# ExperimentBoard.net
KiCad netlist of a schematic drawn in Altium Designer
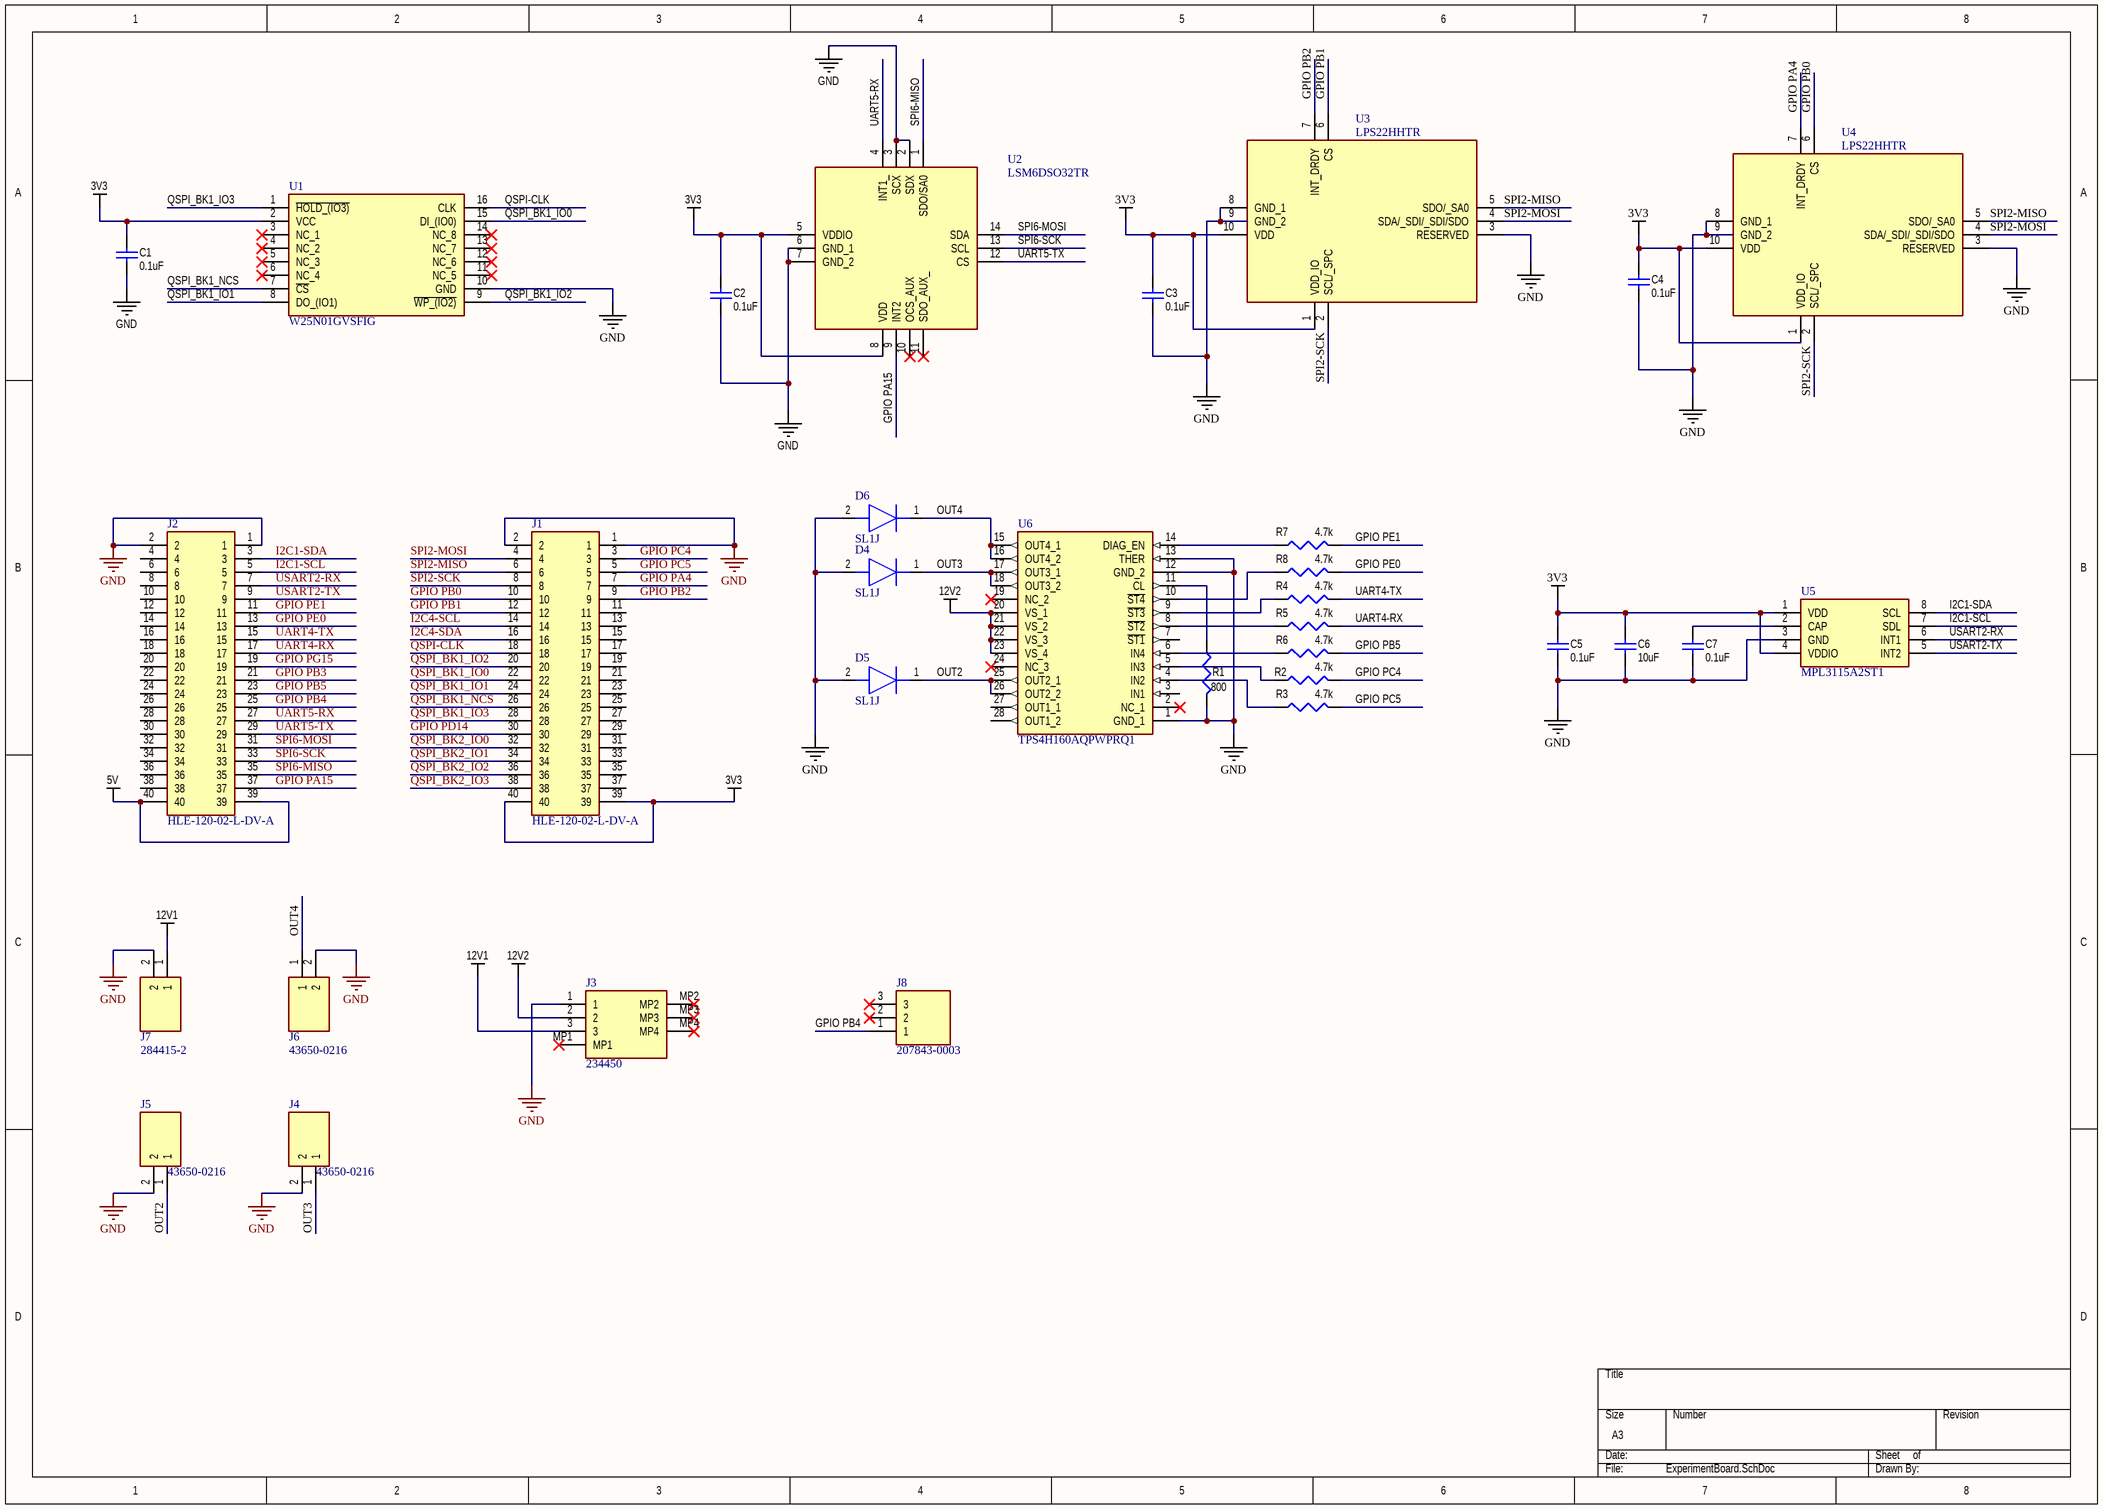
[diagram p0: ExperimentBoard.SchDoc]

(export (version "E")
  (design (tool "Eeschema 10.0.6"))
  (components
    (comp (ref "C1")
      (value "0.1uF")
      (footprint "1608[0603]")
      (description "Capacitor")
      (fields (field (name "PUBLISHER") "Altium Limited"))
      (libsource (lib "Miscellaneous Devices") (part "Cap"))
    )
    (comp (ref "C2")
      (value "0.1uF")
      (footprint "1608[0603]")
      (description "Capacitor")
      (fields (field (name "PUBLISHER") "Altium Limited"))
      (libsource (lib "Miscellaneous Devices") (part "Cap"))
    )
    (comp (ref "C3")
      (value "0.1uF")
      (footprint "1608[0603]")
      (description "Capacitor")
      (fields (field (name "PUBLISHER") "Altium Limited"))
      (libsource (lib "Miscellaneous Devices") (part "Cap"))
    )
    (comp (ref "C4")
      (value "0.1uF")
      (footprint "1608[0603]")
      (description "Capacitor")
      (fields (field (name "PUBLISHER") "Altium Limited"))
      (libsource (lib "Miscellaneous Devices") (part "Cap"))
    )
    (comp (ref "C5")
      (value "0.1uF")
      (footprint "1608[0603]")
      (description "Capacitor")
      (fields (field (name "PUBLISHER") "Altium Limited"))
      (libsource (lib "Miscellaneous Devices") (part "Cap"))
    )
    (comp (ref "C6")
      (value "10uF")
      (footprint "1608[0603]")
      (description "Capacitor")
      (fields (field (name "PUBLISHER") "Altium Limited"))
      (libsource (lib "Miscellaneous Devices") (part "Cap"))
    )
    (comp (ref "C7")
      (value "0.1uF")
      (footprint "1608[0603]")
      (description "Capacitor")
      (fields (field (name "PUBLISHER") "Altium Limited"))
      (libsource (lib "Miscellaneous Devices") (part "Cap"))
    )
    (comp (ref "D4")
      (value "SL1J")
      (footprint "SamacSys:SODFL3718X130N")
      (description "Diode")
      (fields (field (name "MOUSER PART NUMBER") "637-SL1J"))
      (libsource (lib "*") (part "SL1J"))
    )
    (comp (ref "D5")
      (value "SL1J")
      (footprint "SamacSys:SODFL3718X130N")
      (description "Diode")
      (fields (field (name "MOUSER PART NUMBER") "637-SL1J"))
      (libsource (lib "*") (part "SL1J"))
    )
    (comp (ref "D6")
      (value "SL1J")
      (footprint "SamacSys:SODFL3718X130N")
      (description "Diode")
      (fields (field (name "MOUSER PART NUMBER") "637-SL1J"))
      (libsource (lib "*") (part "SL1J"))
    )
    (comp (ref "J1")
      (value "HLE-120-02-L-DV-A")
      (footprint "SamacSys:HLE-120-02-XXX-DV-A")
      (description "Connector")
      (fields (field (name "MOUSER PART NUMBER") "200-HLE12002LDVA"))
      (libsource (lib "*") (part "HLE-120-02-L-DV-A"))
    )
    (comp (ref "J2")
      (value "HLE-120-02-L-DV-A")
      (footprint "SamacSys:HLE-120-02-XXX-DV-A")
      (description "Connector")
      (fields (field (name "MOUSER PART NUMBER") "200-HLE12002LDVA"))
      (libsource (lib "*") (part "HLE-120-02-L-DV-A"))
    )
    (comp (ref "J3")
      (value "234450")
      (footprint "SamacSys:234450")
      (description "Connector")
      (fields (field (name "MOUSER PART NUMBER") "305-234450"))
      (libsource (lib "SamacSys") (part "234450"))
    )
    (comp (ref "J4")
      (value "43650-0216")
      (footprint "SamacSys:43650-02YY_151617")
      (description "Connector")
      (fields (field (name "MOUSER PART NUMBER") "538-43650-0216"))
      (libsource (lib "") (part "43650-0216_1"))
    )
    (comp (ref "J5")
      (value "43650-0216")
      (footprint "SamacSys:43650-02YY_151617")
      (description "Connector")
      (fields (field (name "MOUSER PART NUMBER") "538-43650-0216"))
      (libsource (lib "") (part "43650-0216_1"))
    )
    (comp (ref "J6")
      (value "43650-0216")
      (footprint "SamacSys:43650-02YY_151617")
      (description "Connector")
      (fields (field (name "MOUSER PART NUMBER") "538-43650-0216"))
      (libsource (lib "*") (part "43650-0216"))
    )
    (comp (ref "J7")
      (value "284415-2")
      (footprint "SamacSys:2844152")
      (description "Connector")
      (fields (field (name "MOUSER PART NUMBER") "571-284415-2"))
      (libsource (lib "*") (part "284415-2"))
    )
    (comp (ref "J8")
      (value "207843-0003")
      (footprint "SamacSys:2078430003")
      (description "Connector")
      (fields (field (name "MOUSER PART NUMBER") "538-207843-0003"))
      (libsource (lib "*") (part "207843-0003"))
    )
    (comp (ref "R1")
      (value "800")
      (footprint "J1-0603")
      (description "Resistor")
      (fields (field (name "PUBLISHER") "Altium Limited"))
      (libsource (lib "Miscellaneous Devices") (part "Res3"))
    )
    (comp (ref "R2")
      (value "4.7k")
      (footprint "J1-0603")
      (description "Resistor")
      (fields (field (name "PUBLISHER") "Altium Limited"))
      (libsource (lib "Miscellaneous Devices") (part "Res3"))
    )
    (comp (ref "R3")
      (value "4.7k")
      (footprint "J1-0603")
      (description "Resistor")
      (fields (field (name "PUBLISHER") "Altium Limited"))
      (libsource (lib "Miscellaneous Devices") (part "Res3"))
    )
    (comp (ref "R4")
      (value "4.7k")
      (footprint "J1-0603")
      (description "Resistor")
      (fields (field (name "PUBLISHER") "Altium Limited"))
      (libsource (lib "Miscellaneous Devices") (part "Res3"))
    )
    (comp (ref "R5")
      (value "4.7k")
      (footprint "J1-0603")
      (description "Resistor")
      (fields (field (name "PUBLISHER") "Altium Limited"))
      (libsource (lib "Miscellaneous Devices") (part "Res3"))
    )
    (comp (ref "R6")
      (value "4.7k")
      (footprint "J1-0603")
      (description "Resistor")
      (fields (field (name "PUBLISHER") "Altium Limited"))
      (libsource (lib "Miscellaneous Devices") (part "Res3"))
    )
    (comp (ref "R7")
      (value "4.7k")
      (footprint "J1-0603")
      (description "Resistor")
      (fields (field (name "PUBLISHER") "Altium Limited"))
      (libsource (lib "Miscellaneous Devices") (part "Res3"))
    )
    (comp (ref "R8")
      (value "4.7k")
      (footprint "J1-0603")
      (description "Resistor")
      (fields (field (name "PUBLISHER") "Altium Limited"))
      (libsource (lib "Miscellaneous Devices") (part "Res3"))
    )
    (comp (ref "U1")
      (value "W25N01GVSFIG")
      (footprint "SamacSys:SOIC127P1032X264-16N")
      (description "Integrated Circuit")
      (fields (field (name "MOUSER PART NUMBER") "454-W25N01GVSFIG"))
      (libsource (lib "*") (part "W25N01GVSFIG"))
    )
    (comp (ref "U2")
      (value "LSM6DSO32TR")
      (footprint "SamacSys:LSM6DSO")
      (description "Accelerometer")
      (fields (field (name "MANUFACTURER_PART_NUMBER") "LSM6DSO"))
      (libsource (lib "*") (part "LSM6DSO"))
    )
    (comp (ref "U3")
      (value "LPS22HHTR")
      (footprint "SamacSys:LPS22HHTR")
      (description "Integrated Circuit")
      (fields (field (name "MOUSER PART NUMBER") "511-LPS22HHTR"))
      (libsource (lib "*") (part "LPS22HHTR"))
    )
    (comp (ref "U4")
      (value "LPS22HHTR")
      (footprint "SamacSys:LPS22HHTR")
      (description "Integrated Circuit")
      (fields (field (name "MOUSER PART NUMBER") "511-LPS22HHTR"))
      (libsource (lib "*") (part "LPS22HHTR"))
    )
    (comp (ref "U5")
      (value "MPL3115A2ST1")
      (footprint "SamacSys:MPL3115A2R1")
      (description "Integrated Circuit")
      (fields
        (field (name "MANUFACTURER_PART_NUMBER") "MPL3115A2R1")
        (field (name "MOUSER PART NUMBER") "841-MPL3115A2R1")
      )
      (libsource (lib "*") (part "MPL3115A2R1"))
    )
    (comp (ref "U6")
      (value "TPS4H160AQPWPRQ1")
      (footprint "SamacSys:SOP65P640X120-28N")
      (description "Switch")
      (fields (field (name "MOUSER PART NUMBER") "595-TPS4H160AQPWPRQ1"))
      (libsource (lib "*") (part "TPS4H160AQPWPRQ1"))
    )
  )
  (nets
    (net (code "1") (name "/GPIO PA4") (class "Default")
      (node (ref "J1") (pin "7") (pinfunction "7_7") (pintype "passive"))
      (node (ref "U4") (pin "7") (pinfunction "INT_DRDY_7") (pintype "passive"))
    )
    (net (code "2") (name "/GPIO PA15") (class "Default")
      (node (ref "J2") (pin "37") (pinfunction "37_37") (pintype "passive"))
      (node (ref "U2") (pin "9") (pinfunction "INT2_9") (pintype "passive"))
    )
    (net (code "3") (name "/GPIO PB0") (class "Default")
      (node (ref "J1") (pin "10") (pinfunction "10_10") (pintype "passive"))
      (node (ref "U4") (pin "6") (pinfunction "CS_6") (pintype "passive"))
    )
    (net (code "4") (name "/GPIO PB1") (class "Default")
      (node (ref "J1") (pin "12") (pinfunction "12_12") (pintype "passive"))
      (node (ref "U3") (pin "6") (pinfunction "CS_6") (pintype "passive"))
    )
    (net (code "5") (name "/GPIO PB2") (class "Default")
      (node (ref "J1") (pin "9") (pinfunction "9_9") (pintype "passive"))
      (node (ref "U3") (pin "7") (pinfunction "INT_DRDY_7") (pintype "passive"))
    )
    (net (code "6") (name "/GPIO PB3") (class "Default")
      (node (ref "J2") (pin "21") (pinfunction "21_21") (pintype "passive"))
    )
    (net (code "7") (name "/GPIO PB4") (class "Default")
      (node (ref "J2") (pin "25") (pinfunction "25_25") (pintype "passive"))
      (node (ref "J8") (pin "1") (pinfunction "1_1") (pintype "passive"))
    )
    (net (code "8") (name "/GPIO PB5") (class "Default")
      (node (ref "J2") (pin "23") (pinfunction "23_23") (pintype "passive"))
      (node (ref "R6") (pin "2") (pinfunction "2_2") (pintype "passive"))
    )
    (net (code "9") (name "/GPIO PC4") (class "Default")
      (node (ref "J1") (pin "3") (pinfunction "3_3") (pintype "passive"))
      (node (ref "R2") (pin "2") (pinfunction "2_2") (pintype "passive"))
    )
    (net (code "10") (name "/GPIO PC5") (class "Default")
      (node (ref "J1") (pin "5") (pinfunction "5_5") (pintype "passive"))
      (node (ref "R3") (pin "2") (pinfunction "2_2") (pintype "passive"))
    )
    (net (code "11") (name "/GPIO PD14") (class "Default")
      (node (ref "J1") (pin "30") (pinfunction "30_30") (pintype "passive"))
    )
    (net (code "12") (name "/GPIO PE0") (class "Default")
      (node (ref "J2") (pin "13") (pinfunction "13_13") (pintype "passive"))
      (node (ref "R8") (pin "2") (pinfunction "2_2") (pintype "passive"))
    )
    (net (code "13") (name "/GPIO PE1") (class "Default")
      (node (ref "J2") (pin "11") (pinfunction "11_11") (pintype "passive"))
      (node (ref "R7") (pin "2") (pinfunction "2_2") (pintype "passive"))
    )
    (net (code "14") (name "/GPIO PG15") (class "Default")
      (node (ref "J2") (pin "19") (pinfunction "19_19") (pintype "passive"))
    )
    (net (code "15") (name "/I2C1-SCL") (class "Default")
      (node (ref "J2") (pin "5") (pinfunction "5_5") (pintype "passive"))
      (node (ref "U5") (pin "7") (pinfunction "SDL_7") (pintype "passive"))
    )
    (net (code "16") (name "/I2C1-SDA") (class "Default")
      (node (ref "J2") (pin "3") (pinfunction "3_3") (pintype "passive"))
      (node (ref "U5") (pin "8") (pinfunction "SCL_8") (pintype "passive"))
    )
    (net (code "17") (name "/I2C4-SCL") (class "Default")
      (node (ref "J1") (pin "14") (pinfunction "14_14") (pintype "passive"))
    )
    (net (code "18") (name "/I2C4-SDA") (class "Default")
      (node (ref "J1") (pin "16") (pinfunction "16_16") (pintype "passive"))
    )
    (net (code "19") (name "/OUT2") (class "Default")
      (node (ref "D5") (pin "1") (pinfunction "K_1") (pintype "passive"))
      (node (ref "J5") (pin "1") (pinfunction "1_1") (pintype "passive"))
      (node (ref "U6") (pin "25") (pinfunction "OUT2_1_25") (pintype "output"))
      (node (ref "U6") (pin "26") (pinfunction "OUT2_2_26") (pintype "output"))
    )
    (net (code "20") (name "/OUT3") (class "Default")
      (node (ref "D4") (pin "1") (pinfunction "K_1") (pintype "passive"))
      (node (ref "J4") (pin "1") (pinfunction "1_1") (pintype "passive"))
      (node (ref "U6") (pin "17") (pinfunction "OUT3_1_17") (pintype "output"))
      (node (ref "U6") (pin "18") (pinfunction "OUT3_2_18") (pintype "output"))
    )
    (net (code "21") (name "/OUT4") (class "Default")
      (node (ref "D6") (pin "1") (pinfunction "K_1") (pintype "passive"))
      (node (ref "J6") (pin "1") (pinfunction "1_1") (pintype "passive"))
      (node (ref "U6") (pin "15") (pinfunction "OUT4_1_15") (pintype "output"))
      (node (ref "U6") (pin "16") (pinfunction "OUT4_2_16") (pintype "output"))
    )
    (net (code "22") (name "/QSPI-CLK") (class "Default")
      (node (ref "J1") (pin "18") (pinfunction "18_18") (pintype "passive"))
      (node (ref "U1") (pin "16") (pinfunction "CLK_16") (pintype "passive"))
    )
    (net (code "23") (name "/QSPI_BK1_IO0") (class "Default")
      (node (ref "J1") (pin "22") (pinfunction "22_22") (pintype "passive"))
      (node (ref "U1") (pin "15") (pinfunction "DI_(IO0)_15") (pintype "passive"))
    )
    (net (code "24") (name "/QSPI_BK1_IO1") (class "Default")
      (node (ref "J1") (pin "24") (pinfunction "24_24") (pintype "passive"))
      (node (ref "U1") (pin "8") (pinfunction "DO_(IO1)_8") (pintype "passive"))
    )
    (net (code "25") (name "/QSPI_BK1_IO2") (class "Default")
      (node (ref "J1") (pin "20") (pinfunction "20_20") (pintype "passive"))
      (node (ref "U1") (pin "9") (pinfunction "~{WP_(IO2)}_9") (pintype "passive"))
    )
    (net (code "26") (name "/QSPI_BK1_IO3") (class "Default")
      (node (ref "J1") (pin "28") (pinfunction "28_28") (pintype "passive"))
      (node (ref "U1") (pin "1") (pinfunction "~{HOLD_(IO3)}_1") (pintype "passive"))
    )
    (net (code "27") (name "/QSPI_BK1_NCS") (class "Default")
      (node (ref "J1") (pin "26") (pinfunction "26_26") (pintype "passive"))
      (node (ref "U1") (pin "7") (pinfunction "~{CS}_7") (pintype "passive"))
    )
    (net (code "28") (name "/QSPI_BK2_IO0") (class "Default")
      (node (ref "J1") (pin "32") (pinfunction "32_32") (pintype "passive"))
    )
    (net (code "29") (name "/QSPI_BK2_IO1") (class "Default")
      (node (ref "J1") (pin "34") (pinfunction "34_34") (pintype "passive"))
    )
    (net (code "30") (name "/QSPI_BK2_IO2") (class "Default")
      (node (ref "J1") (pin "36") (pinfunction "36_36") (pintype "passive"))
    )
    (net (code "31") (name "/QSPI_BK2_IO3") (class "Default")
      (node (ref "J1") (pin "38") (pinfunction "38_38") (pintype "passive"))
    )
    (net (code "32") (name "/SPI2-MISO") (class "Default")
      (node (ref "J1") (pin "6") (pinfunction "6_6") (pintype "passive"))
      (node (ref "U3") (pin "5") (pinfunction "SDO/_SA0_5") (pintype "passive"))
      (node (ref "U4") (pin "5") (pinfunction "SDO/_SA0_5") (pintype "passive"))
    )
    (net (code "33") (name "/SPI2-MOSI") (class "Default")
      (node (ref "J1") (pin "4") (pinfunction "4_4") (pintype "passive"))
      (node (ref "U3") (pin "4") (pinfunction "SDA/_SDI/_SDI/SDO_4") (pintype "passive"))
      (node (ref "U4") (pin "4") (pinfunction "SDA/_SDI/_SDI/SDO_4") (pintype "passive"))
    )
    (net (code "34") (name "/SPI2-SCK") (class "Default")
      (node (ref "J1") (pin "8") (pinfunction "8_8") (pintype "passive"))
      (node (ref "U3") (pin "2") (pinfunction "SCL/_SPC_2") (pintype "passive"))
      (node (ref "U4") (pin "2") (pinfunction "SCL/_SPC_2") (pintype "passive"))
    )
    (net (code "35") (name "/SPI6-MISO") (class "Default")
      (node (ref "J2") (pin "35") (pinfunction "35_35") (pintype "passive"))
      (node (ref "U2") (pin "1") (pinfunction "SDO/SA0_1") (pintype "passive"))
    )
    (net (code "36") (name "/SPI6-MOSI") (class "Default")
      (node (ref "J2") (pin "31") (pinfunction "31_31") (pintype "passive"))
      (node (ref "U2") (pin "14") (pinfunction "SDA_14") (pintype "passive"))
    )
    (net (code "37") (name "/SPI6-SCK") (class "Default")
      (node (ref "J2") (pin "33") (pinfunction "33_33") (pintype "passive"))
      (node (ref "U2") (pin "13") (pinfunction "SCL_13") (pintype "passive"))
    )
    (net (code "38") (name "/UART4-RX") (class "Default")
      (node (ref "J2") (pin "17") (pinfunction "17_17") (pintype "passive"))
      (node (ref "R5") (pin "2") (pinfunction "2_2") (pintype "passive"))
    )
    (net (code "39") (name "/UART4-TX") (class "Default")
      (node (ref "J2") (pin "15") (pinfunction "15_15") (pintype "passive"))
      (node (ref "R4") (pin "2") (pinfunction "2_2") (pintype "passive"))
    )
    (net (code "40") (name "/UART5-RX") (class "Default")
      (node (ref "J2") (pin "27") (pinfunction "27_27") (pintype "passive"))
      (node (ref "U2") (pin "4") (pinfunction "INT1__4") (pintype "passive"))
    )
    (net (code "41") (name "/UART5-TX") (class "Default")
      (node (ref "J2") (pin "29") (pinfunction "29_29") (pintype "passive"))
      (node (ref "U2") (pin "12") (pinfunction "CS_12") (pintype "passive"))
    )
    (net (code "42") (name "/USART2-RX") (class "Default")
      (node (ref "J2") (pin "7") (pinfunction "7_7") (pintype "passive"))
      (node (ref "U5") (pin "6") (pinfunction "INT1_6") (pintype "passive"))
    )
    (net (code "43") (name "/USART2-TX") (class "Default")
      (node (ref "J2") (pin "9") (pinfunction "9_9") (pintype "passive"))
      (node (ref "U5") (pin "5") (pinfunction "INT2_5") (pintype "passive"))
    )
    (net (code "44") (name "3V3") (class "Default")
      (node (ref "C1") (pin "2") (pinfunction "2_2") (pintype "passive"))
      (node (ref "C2") (pin "2") (pinfunction "2_2") (pintype "passive"))
      (node (ref "C3") (pin "2") (pinfunction "2_2") (pintype "passive"))
      (node (ref "C4") (pin "2") (pinfunction "2_2") (pintype "passive"))
      (node (ref "C5") (pin "1") (pinfunction "1_1") (pintype "passive"))
      (node (ref "C6") (pin "1") (pinfunction "1_1") (pintype "passive"))
      (node (ref "J1") (pin "39") (pinfunction "39_39") (pintype "passive"))
      (node (ref "J1") (pin "40") (pinfunction "40_40") (pintype "passive"))
      (node (ref "U1") (pin "2") (pinfunction "VCC_2") (pintype "passive"))
      (node (ref "U2") (pin "5") (pinfunction "VDDIO_5") (pintype "passive"))
      (node (ref "U2") (pin "8") (pinfunction "VDD_8") (pintype "passive"))
      (node (ref "U3") (pin "1") (pinfunction "VDD_IO_1") (pintype "passive"))
      (node (ref "U3") (pin "10") (pinfunction "VDD_10") (pintype "passive"))
      (node (ref "U4") (pin "1") (pinfunction "VDD_IO_1") (pintype "passive"))
      (node (ref "U4") (pin "10") (pinfunction "VDD_10") (pintype "passive"))
      (node (ref "U5") (pin "1") (pinfunction "VDD_1") (pintype "passive"))
      (node (ref "U5") (pin "4") (pinfunction "VDDIO_4") (pintype "passive"))
    )
    (net (code "45") (name "5V") (class "Default")
      (node (ref "J2") (pin "39") (pinfunction "39_39") (pintype "passive"))
      (node (ref "J2") (pin "40") (pinfunction "40_40") (pintype "passive"))
    )
    (net (code "46") (name "12V1") (class "Default")
      (node (ref "J3") (pin "3") (pinfunction "3_3") (pintype "passive"))
      (node (ref "J7") (pin "1") (pinfunction "1_1") (pintype "passive"))
    )
    (net (code "47") (name "12V2") (class "Default")
      (node (ref "J3") (pin "2") (pinfunction "2_2") (pintype "passive"))
      (node (ref "U6") (pin "20") (pinfunction "VS_1_20") (pintype "power_in"))
      (node (ref "U6") (pin "21") (pinfunction "VS_2_21") (pintype "power_in"))
      (node (ref "U6") (pin "22") (pinfunction "VS_3_22") (pintype "power_in"))
      (node (ref "U6") (pin "23") (pinfunction "VS_4_23") (pintype "power_in"))
    )
    (net (code "48") (name "GND") (class "Default")
      (node (ref "C1") (pin "1") (pinfunction "1_1") (pintype "passive"))
      (node (ref "C2") (pin "1") (pinfunction "1_1") (pintype "passive"))
      (node (ref "C3") (pin "1") (pinfunction "1_1") (pintype "passive"))
      (node (ref "C4") (pin "1") (pinfunction "1_1") (pintype "passive"))
      (node (ref "C5") (pin "2") (pinfunction "2_2") (pintype "passive"))
      (node (ref "C6") (pin "2") (pinfunction "2_2") (pintype "passive"))
      (node (ref "C7") (pin "2") (pinfunction "2_2") (pintype "passive"))
      (node (ref "D4") (pin "2") (pinfunction "A_2") (pintype "passive"))
      (node (ref "D5") (pin "2") (pinfunction "A_2") (pintype "passive"))
      (node (ref "D6") (pin "2") (pinfunction "A_2") (pintype "passive"))
      (node (ref "J1") (pin "1") (pinfunction "1_1") (pintype "passive"))
      (node (ref "J1") (pin "2") (pinfunction "2_2") (pintype "passive"))
      (node (ref "J2") (pin "1") (pinfunction "1_1") (pintype "passive"))
      (node (ref "J2") (pin "2") (pinfunction "2_2") (pintype "passive"))
      (node (ref "J3") (pin "1") (pinfunction "1_1") (pintype "passive"))
      (node (ref "J4") (pin "2") (pinfunction "2_2") (pintype "passive"))
      (node (ref "J5") (pin "2") (pinfunction "2_2") (pintype "passive"))
      (node (ref "J6") (pin "2") (pinfunction "2_2") (pintype "passive"))
      (node (ref "J7") (pin "2") (pinfunction "2_2") (pintype "passive"))
      (node (ref "R1") (pin "2") (pinfunction "2_2") (pintype "passive"))
      (node (ref "U1") (pin "10") (pinfunction "GND_10") (pintype "passive"))
      (node (ref "U2") (pin "2") (pinfunction "SDX_2") (pintype "passive"))
      (node (ref "U2") (pin "3") (pinfunction "SCX_3") (pintype "passive"))
      (node (ref "U2") (pin "6") (pinfunction "GND_1_6") (pintype "passive"))
      (node (ref "U2") (pin "7") (pinfunction "GND_2_7") (pintype "passive"))
      (node (ref "U3") (pin "3") (pinfunction "RESERVED_3") (pintype "passive"))
      (node (ref "U3") (pin "8") (pinfunction "GND_1_8") (pintype "passive"))
      (node (ref "U3") (pin "9") (pinfunction "GND_2_9") (pintype "passive"))
      (node (ref "U4") (pin "3") (pinfunction "RESERVED_3") (pintype "passive"))
      (node (ref "U4") (pin "8") (pinfunction "GND_1_8") (pintype "passive"))
      (node (ref "U4") (pin "9") (pinfunction "GND_2_9") (pintype "passive"))
      (node (ref "U5") (pin "3") (pinfunction "GND_3") (pintype "passive"))
      (node (ref "U6") (pin "1") (pinfunction "GND_1_1") (pintype "power_in"))
      (node (ref "U6") (pin "12") (pinfunction "GND_2_12") (pintype "power_in"))
      (node (ref "U6") (pin "13") (pinfunction "THER_13") (pintype "input"))
    )
    (net (code "49") (name "Net-(U5-CAP)") (class "Default")
      (node (ref "C7") (pin "1") (pinfunction "1_1") (pintype "passive"))
      (node (ref "U5") (pin "2") (pinfunction "CAP_2") (pintype "passive"))
    )
    (net (code "50") (name "Net-(U6-CL)") (class "Default")
      (node (ref "R1") (pin "1") (pinfunction "1_1") (pintype "passive"))
      (node (ref "U6") (pin "11") (pinfunction "CL_11") (pintype "output"))
    )
    (net (code "51") (name "Net-(U6-DIAG_EN)") (class "Default")
      (node (ref "R7") (pin "1") (pinfunction "1_1") (pintype "passive"))
      (node (ref "U6") (pin "14") (pinfunction "DIAG_EN_14") (pintype "input"))
    )
    (net (code "52") (name "Net-(U6-IN2)") (class "Default")
      (node (ref "R3") (pin "1") (pinfunction "1_1") (pintype "passive"))
      (node (ref "U6") (pin "4") (pinfunction "IN2_4") (pintype "input"))
    )
    (net (code "53") (name "Net-(U6-IN3)") (class "Default")
      (node (ref "R2") (pin "1") (pinfunction "1_1") (pintype "passive"))
      (node (ref "U6") (pin "5") (pinfunction "IN3_5") (pintype "input"))
    )
    (net (code "54") (name "Net-(U6-IN4)") (class "Default")
      (node (ref "R6") (pin "1") (pinfunction "1_1") (pintype "passive"))
      (node (ref "U6") (pin "6") (pinfunction "IN4_6") (pintype "input"))
    )
    (net (code "55") (name "Net-(U6-~{ST2})") (class "Default")
      (node (ref "R5") (pin "1") (pinfunction "1_1") (pintype "passive"))
      (node (ref "U6") (pin "8") (pinfunction "~{ST2}_8") (pintype "output"))
    )
    (net (code "56") (name "Net-(U6-~{ST3})") (class "Default")
      (node (ref "R4") (pin "1") (pinfunction "1_1") (pintype "passive"))
      (node (ref "U6") (pin "9") (pinfunction "~{ST3}_9") (pintype "output"))
    )
    (net (code "57") (name "Net-(U6-~{ST4})") (class "Default")
      (node (ref "R8") (pin "1") (pinfunction "1_1") (pintype "passive"))
      (node (ref "U6") (pin "10") (pinfunction "~{ST4}_10") (pintype "output"))
    )
    (net (code "58") (name "unconnected-(J1-Pad11)") (class "Default")
      (node (ref "J1") (pin "11") (pinfunction "11_11") (pintype "passive"))
    )
    (net (code "59") (name "unconnected-(J1-Pad13)") (class "Default")
      (node (ref "J1") (pin "13") (pinfunction "13_13") (pintype "passive"))
    )
    (net (code "60") (name "unconnected-(J1-Pad15)") (class "Default")
      (node (ref "J1") (pin "15") (pinfunction "15_15") (pintype "passive"))
    )
    (net (code "61") (name "unconnected-(J1-Pad17)") (class "Default")
      (node (ref "J1") (pin "17") (pinfunction "17_17") (pintype "passive"))
    )
    (net (code "62") (name "unconnected-(J1-Pad19)") (class "Default")
      (node (ref "J1") (pin "19") (pinfunction "19_19") (pintype "passive"))
    )
    (net (code "63") (name "unconnected-(J1-Pad21)") (class "Default")
      (node (ref "J1") (pin "21") (pinfunction "21_21") (pintype "passive"))
    )
    (net (code "64") (name "unconnected-(J1-Pad23)") (class "Default")
      (node (ref "J1") (pin "23") (pinfunction "23_23") (pintype "passive"))
    )
    (net (code "65") (name "unconnected-(J1-Pad25)") (class "Default")
      (node (ref "J1") (pin "25") (pinfunction "25_25") (pintype "passive"))
    )
    (net (code "66") (name "unconnected-(J1-Pad27)") (class "Default")
      (node (ref "J1") (pin "27") (pinfunction "27_27") (pintype "passive"))
    )
    (net (code "67") (name "unconnected-(J1-Pad29)") (class "Default")
      (node (ref "J1") (pin "29") (pinfunction "29_29") (pintype "passive"))
    )
    (net (code "68") (name "unconnected-(J1-Pad31)") (class "Default")
      (node (ref "J1") (pin "31") (pinfunction "31_31") (pintype "passive"))
    )
    (net (code "69") (name "unconnected-(J1-Pad33)") (class "Default")
      (node (ref "J1") (pin "33") (pinfunction "33_33") (pintype "passive"))
    )
    (net (code "70") (name "unconnected-(J1-Pad35)") (class "Default")
      (node (ref "J1") (pin "35") (pinfunction "35_35") (pintype "passive"))
    )
    (net (code "71") (name "unconnected-(J1-Pad37)") (class "Default")
      (node (ref "J1") (pin "37") (pinfunction "37_37") (pintype "passive"))
    )
    (net (code "72") (name "unconnected-(J2-Pad4)") (class "Default")
      (node (ref "J2") (pin "4") (pinfunction "4_4") (pintype "passive"))
    )
    (net (code "73") (name "unconnected-(J2-Pad6)") (class "Default")
      (node (ref "J2") (pin "6") (pinfunction "6_6") (pintype "passive"))
    )
    (net (code "74") (name "unconnected-(J2-Pad8)") (class "Default")
      (node (ref "J2") (pin "8") (pinfunction "8_8") (pintype "passive"))
    )
    (net (code "75") (name "unconnected-(J2-Pad10)") (class "Default")
      (node (ref "J2") (pin "10") (pinfunction "10_10") (pintype "passive"))
    )
    (net (code "76") (name "unconnected-(J2-Pad12)") (class "Default")
      (node (ref "J2") (pin "12") (pinfunction "12_12") (pintype "passive"))
    )
    (net (code "77") (name "unconnected-(J2-Pad14)") (class "Default")
      (node (ref "J2") (pin "14") (pinfunction "14_14") (pintype "passive"))
    )
    (net (code "78") (name "unconnected-(J2-Pad16)") (class "Default")
      (node (ref "J2") (pin "16") (pinfunction "16_16") (pintype "passive"))
    )
    (net (code "79") (name "unconnected-(J2-Pad18)") (class "Default")
      (node (ref "J2") (pin "18") (pinfunction "18_18") (pintype "passive"))
    )
    (net (code "80") (name "unconnected-(J2-Pad20)") (class "Default")
      (node (ref "J2") (pin "20") (pinfunction "20_20") (pintype "passive"))
    )
    (net (code "81") (name "unconnected-(J2-Pad22)") (class "Default")
      (node (ref "J2") (pin "22") (pinfunction "22_22") (pintype "passive"))
    )
    (net (code "82") (name "unconnected-(J2-Pad24)") (class "Default")
      (node (ref "J2") (pin "24") (pinfunction "24_24") (pintype "passive"))
    )
    (net (code "83") (name "unconnected-(J2-Pad26)") (class "Default")
      (node (ref "J2") (pin "26") (pinfunction "26_26") (pintype "passive"))
    )
    (net (code "84") (name "unconnected-(J2-Pad28)") (class "Default")
      (node (ref "J2") (pin "28") (pinfunction "28_28") (pintype "passive"))
    )
    (net (code "85") (name "unconnected-(J2-Pad30)") (class "Default")
      (node (ref "J2") (pin "30") (pinfunction "30_30") (pintype "passive"))
    )
    (net (code "86") (name "unconnected-(J2-Pad32)") (class "Default")
      (node (ref "J2") (pin "32") (pinfunction "32_32") (pintype "passive"))
    )
    (net (code "87") (name "unconnected-(J2-Pad34)") (class "Default")
      (node (ref "J2") (pin "34") (pinfunction "34_34") (pintype "passive"))
    )
    (net (code "88") (name "unconnected-(J2-Pad36)") (class "Default")
      (node (ref "J2") (pin "36") (pinfunction "36_36") (pintype "passive"))
    )
    (net (code "89") (name "unconnected-(J2-Pad38)") (class "Default")
      (node (ref "J2") (pin "38") (pinfunction "38_38") (pintype "passive"))
    )
    (net (code "90") (name "unconnected-(J3-PadMP1)") (class "Default")
      (node (ref "J3") (pin "MP1") (pinfunction "MP1_MP1") (pintype "passive+no_connect"))
    )
    (net (code "91") (name "unconnected-(J3-PadMP2)") (class "Default")
      (node (ref "J3") (pin "MP2") (pinfunction "MP2_MP2") (pintype "passive+no_connect"))
    )
    (net (code "92") (name "unconnected-(J3-PadMP3)") (class "Default")
      (node (ref "J3") (pin "MP3") (pinfunction "MP3_MP3") (pintype "passive+no_connect"))
    )
    (net (code "93") (name "unconnected-(J3-PadMP4)") (class "Default")
      (node (ref "J3") (pin "MP4") (pinfunction "MP4_MP4") (pintype "passive+no_connect"))
    )
    (net (code "94") (name "unconnected-(J8-Pad2)") (class "Default")
      (node (ref "J8") (pin "2") (pinfunction "2_2") (pintype "passive+no_connect"))
    )
    (net (code "95") (name "unconnected-(J8-Pad3)") (class "Default")
      (node (ref "J8") (pin "3") (pinfunction "3_3") (pintype "passive+no_connect"))
    )
    (net (code "96") (name "unconnected-(U1-NC_1-Pad3)") (class "Default")
      (node (ref "U1") (pin "3") (pinfunction "NC_1_3") (pintype "passive+no_connect"))
    )
    (net (code "97") (name "unconnected-(U1-NC_2-Pad4)") (class "Default")
      (node (ref "U1") (pin "4") (pinfunction "NC_2_4") (pintype "passive+no_connect"))
    )
    (net (code "98") (name "unconnected-(U1-NC_3-Pad5)") (class "Default")
      (node (ref "U1") (pin "5") (pinfunction "NC_3_5") (pintype "passive+no_connect"))
    )
    (net (code "99") (name "unconnected-(U1-NC_4-Pad6)") (class "Default")
      (node (ref "U1") (pin "6") (pinfunction "NC_4_6") (pintype "passive+no_connect"))
    )
    (net (code "100") (name "unconnected-(U1-NC_5-Pad11)") (class "Default")
      (node (ref "U1") (pin "11") (pinfunction "NC_5_11") (pintype "passive+no_connect"))
    )
    (net (code "101") (name "unconnected-(U1-NC_6-Pad12)") (class "Default")
      (node (ref "U1") (pin "12") (pinfunction "NC_6_12") (pintype "passive+no_connect"))
    )
    (net (code "102") (name "unconnected-(U1-NC_7-Pad13)") (class "Default")
      (node (ref "U1") (pin "13") (pinfunction "NC_7_13") (pintype "passive+no_connect"))
    )
    (net (code "103") (name "unconnected-(U1-NC_8-Pad14)") (class "Default")
      (node (ref "U1") (pin "14") (pinfunction "NC_8_14") (pintype "passive+no_connect"))
    )
    (net (code "104") (name "unconnected-(U2-OCS_AUX-Pad10)") (class "Default")
      (node (ref "U2") (pin "10") (pinfunction "OCS_AUX_10") (pintype "passive+no_connect"))
    )
    (net (code "105") (name "unconnected-(U2-SDO_AUX_-Pad11)") (class "Default")
      (node (ref "U2") (pin "11") (pinfunction "SDO_AUX__11") (pintype "passive+no_connect"))
    )
    (net (code "106") (name "unconnected-(U6-IN1-Pad3)") (class "Default")
      (node (ref "U6") (pin "3") (pinfunction "IN1_3") (pintype "input"))
    )
    (net (code "107") (name "unconnected-(U6-NC_1-Pad2)") (class "Default")
      (node (ref "U6") (pin "2") (pinfunction "NC_1_2") (pintype "passive+no_connect"))
    )
    (net (code "108") (name "unconnected-(U6-NC_2-Pad19)") (class "Default")
      (node (ref "U6") (pin "19") (pinfunction "NC_2_19") (pintype "passive+no_connect"))
    )
    (net (code "109") (name "unconnected-(U6-NC_3-Pad24)") (class "Default")
      (node (ref "U6") (pin "24") (pinfunction "NC_3_24") (pintype "passive+no_connect"))
    )
    (net (code "110") (name "unconnected-(U6-OUT1_1-Pad27)") (class "Default")
      (node (ref "U6") (pin "27") (pinfunction "OUT1_1_27") (pintype "output"))
    )
    (net (code "111") (name "unconnected-(U6-OUT1_2-Pad28)") (class "Default")
      (node (ref "U6") (pin "28") (pinfunction "OUT1_2_28") (pintype "output"))
    )
    (net (code "112") (name "unconnected-(U6-~{ST1}-Pad7)") (class "Default")
      (node (ref "U6") (pin "7") (pinfunction "~{ST1}_7") (pintype "output"))
    )
  )
)
